# DOT_LED.net
KiCad netlist of a schematic drawn in Altium Designer
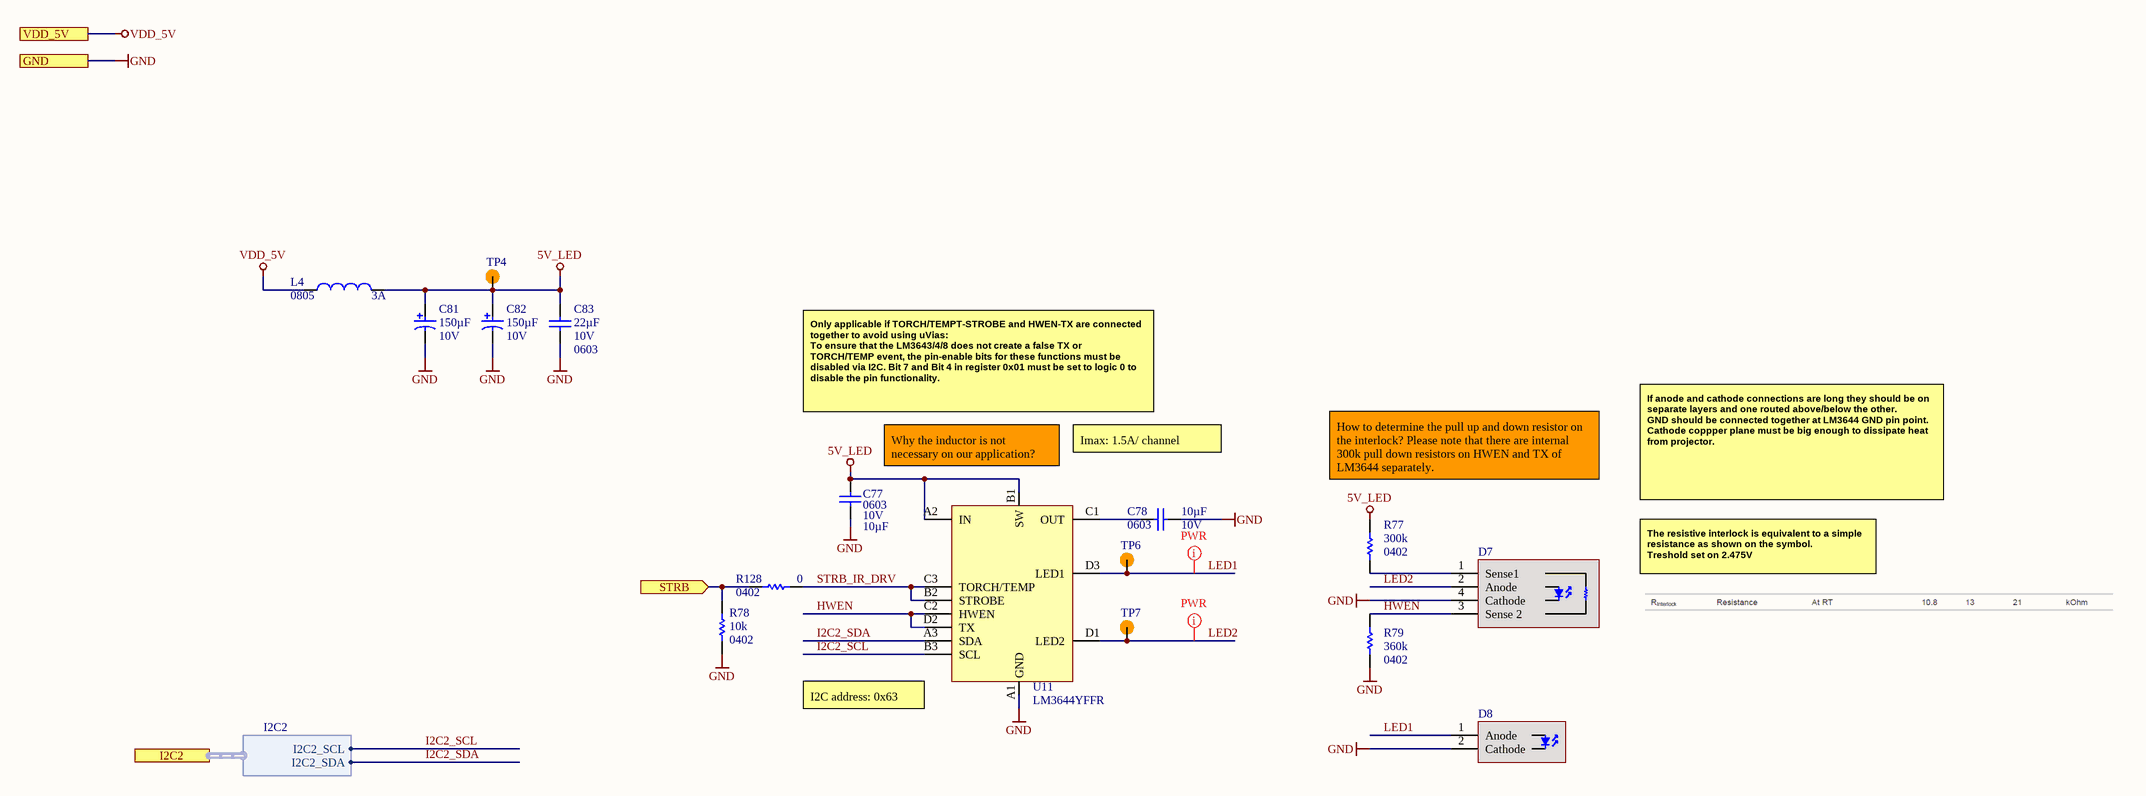
[diagram p0: DOT_LED.SchDoc]

(export (version "E")
  (design (tool "Eeschema 10.0.6"))
  (components
    (comp (ref "C77")
      (value "10µF")
      (footprint "CAPC0603(1608)100_L")
      (description "CAP CER 10UF 10V X5R 0603 20%")
      (fields
        (field (name "CASE/PACKAGE") "0603")
        (field (name "TOLERANCE") "20%")
        (field (name "VOLTAGE RATING") "10V")
        (field (name "Comment") "GRM188R61A106ME69D")
      )
      (libsource (lib "Luxonis LLC") (part "LLL153C70G474ME17E"))
    )
    (comp (ref "C78")
      (value "10µF")
      (footprint "CAPC0603(1608)100_L")
      (description "CAP CER 10UF 10V X5R 0603 20%")
      (fields
        (field (name "CASE/PACKAGE") "0603")
        (field (name "TOLERANCE") "20%")
        (field (name "VOLTAGE RATING") "10V")
        (field (name "Comment") "GRM188R61A106ME69D")
      )
      (libsource (lib "Luxonis LLC") (part "LLL153C70G474ME17E"))
    )
    (comp (ref "C81")
      (value "150µF")
      (footprint "RESTL1210(3225)_L")
      (description "CAP TAL 150UF 10V 20%")
      (fields
        (field (name "TOLERANCE") "20%")
        (field (name "VOLTAGE RATING") "10V")
        (field (name "Comment") "TLJB157M010R0500")
      )
      (libsource (lib "Luxonis LLC") (part "TLJB157M010R0500"))
    )
    (comp (ref "C82")
      (value "150µF")
      (footprint "RESTL1210(3225)_L")
      (description "CAP TAL 150UF 10V 20%")
      (fields
        (field (name "TOLERANCE") "20%")
        (field (name "VOLTAGE RATING") "10V")
        (field (name "Comment") "TLJB157M010R0500")
      )
      (libsource (lib "Luxonis LLC") (part "TLJB157M010R0500"))
    )
    (comp (ref "C83")
      (value "22µF")
      (footprint "CAPC0603(1608)100_N")
      (description "CAP CER 22UF 10V X5R 0603 20%")
      (fields
        (field (name "VOLTAGE RATING") "10V")
        (field (name "TOLERANCE") "20%")
        (field (name "CASE/PACKAGE") "0603")
        (field (name "Comment") "GRM188R61A226ME15D")
      )
      (libsource (lib "Luxonis LLC") (part "GRM188R61C475KAAJD"))
    )
    (comp (ref "D7")
      (value "BELAGO1.1")
      (footprint "Belago1.1")
      (description "Dot-Pattern Infrared Illuminator for 3D Stereoscopic\r\nImaging AQAA-20")
      (libsource (lib "Luxonis LLC") (part "BELAGO1.1"))
    )
    (comp (ref "D8")
      (value "SFH 4725AS")
      (footprint "SFH 4715AS")
      (description "OSLON Black Series (940 nm) - 80°")
      (libsource (lib "Luxonis LLC") (part "SFH 4725AS"))
    )
    (comp (ref "L4")
      (value "742792011")
      (footprint "SMD-0805")
      (description "Ferrite Chip, 1 Function(s), 3A, 2 Pin(s)")
      (fields (field (name "CURRENT RATING") "3A") (field (name "CASE/PACKAGE") "0805"))
      (libsource (lib "Luxonis LLC") (part "IND-2"))
    )
    (comp (ref "R77")
      (value "300k")
      (footprint "RESC0402(1005)_N")
      (description "RES SMD 300K OHM 1% 1/16W 0402")
      (fields
        (field (name "CASE/PACKAGE") "0402")
        (field (name "TOLERANCE") "1%")
        (field (name "Comment") "RC0402FR-07300KL")
      )
      (libsource (lib "Luxonis LLC") (part "Default resistor symbol"))
    )
    (comp (ref "R78")
      (value "10k")
      (footprint "RESC0402(1005)_N")
      (description "RES SMD 10K OHM 1% 1/16W 0402")
      (fields
        (field (name "CASE/PACKAGE") "0402")
        (field (name "TOLERANCE") "1%")
        (field (name "Comment") "RC0402FR-1310KL")
      )
      (libsource (lib "Luxonis LLC") (part "RC0402FR-0722RL_1"))
    )
    (comp (ref "R79")
      (value "360k")
      (footprint "RESC0402(1005)_N")
      (description "RES SMD 360K OHM 1% 1/16W 0402")
      (fields
        (field (name "CASE/PACKAGE") "0402")
        (field (name "TOLERANCE") "1%")
        (field (name "Comment") "RC0402FR-07360KL")
      )
      (libsource (lib "Luxonis LLC") (part "Default resistor symbol"))
    )
    (comp (ref "R128")
      (value "0")
      (footprint "RESC0402(1005)_L")
      (description "RES SMD 0 OHM 5% 1/16W 0402")
      (fields
        (field (name "CASE/PACKAGE") "0402")
        (field (name "TOLERANCE") "5%")
        (field (name "Comment") "CRCW04020000Z0ED")
      )
      (libsource (lib "Luxonis LLC") (part "Default resistor symbol"))
    )
    (comp (ref "TP4")
      (value "TEST_POINT")
      (footprint "TP075_150_NS")
      (libsource (lib "Luxonis LLC") (part "TEST_POINT"))
    )
    (comp (ref "TP6")
      (value "TEST_POINT")
      (footprint "TP075_150_NS")
      (libsource (lib "Luxonis LLC") (part "TEST_POINT"))
    )
    (comp (ref "TP7")
      (value "TEST_POINT")
      (footprint "TP075_150_NS")
      (libsource (lib "Luxonis LLC") (part "TEST_POINT"))
    )
    (comp (ref "U11")
      (value "LM3644YFFR")
      (footprint "LM3644YFFR")
      (description "LED Driver, 2-Segment, PBGA12")
      (libsource (lib "Luxonis LLC") (part "LM3644"))
    )
  )
  (nets
    (net (code "2") (name "/HWEN") (class "Default")
      (node (ref "D7") (pin "3") (pinfunction "Sense_2_3") (pintype "passive"))
      (node (ref "R79") (pin "2") (pinfunction "2_2") (pintype "passive"))
      (node (ref "U11") (pin "C2") (pinfunction "HWEN_C2") (pintype "passive"))
      (node (ref "U11") (pin "D2") (pinfunction "TX_D2") (pintype "passive"))
    )
    (net (code "3") (name "/I2C2_SCL") (class "Default")
      (node (ref "U11") (pin "B3") (pinfunction "SCL_B3") (pintype "passive"))
    )
    (net (code "4") (name "/I2C2_SDA") (class "Default")
      (node (ref "U11") (pin "A3") (pinfunction "SDA_A3") (pintype "passive"))
    )
    (net (code "5") (name "/LED1") (class "Default")
      (node (ref "D8") (pin "1") (pinfunction "Anode_1") (pintype "passive"))
      (node (ref "TP6") (pin "1") (pintype "passive"))
      (node (ref "U11") (pin "D3") (pinfunction "LED1_D3") (pintype "passive"))
    )
    (net (code "6") (name "/LED2") (class "Default")
      (node (ref "D7") (pin "2") (pinfunction "Anode_2") (pintype "passive"))
      (node (ref "TP7") (pin "1") (pintype "passive"))
      (node (ref "U11") (pin "D1") (pinfunction "LED2_D1") (pintype "passive"))
    )
    (net (code "7") (name "/STRB") (class "Default")
      (node (ref "R128") (pin "2") (pinfunction "2_2") (pintype "passive"))
      (node (ref "R78") (pin "2") (pinfunction "2_2") (pintype "passive"))
    )
    (net (code "8") (name "/STRB_IR_DRV") (class "Default")
      (node (ref "R128") (pin "1") (pinfunction "1_1") (pintype "passive"))
      (node (ref "U11") (pin "B2") (pinfunction "STROBE_B2") (pintype "passive"))
      (node (ref "U11") (pin "C3") (pinfunction "TORCH/TEMP_C3") (pintype "passive"))
    )
    (net (code "10") (name "5V_LED") (class "Default")
      (node (ref "C77") (pin "2") (pinfunction "2_2") (pintype "passive"))
      (node (ref "C81") (pin "1") (pinfunction "1_1") (pintype "passive"))
      (node (ref "C82") (pin "1") (pinfunction "1_1") (pintype "passive"))
      (node (ref "C83") (pin "2") (pinfunction "2_2") (pintype "passive"))
      (node (ref "L4") (pin "2") (pinfunction "2_2") (pintype "passive"))
      (node (ref "R77") (pin "2") (pinfunction "2_2") (pintype "passive"))
      (node (ref "TP4") (pin "1") (pintype "passive"))
      (node (ref "U11") (pin "A2") (pinfunction "IN_A2") (pintype "passive"))
      (node (ref "U11") (pin "B1") (pinfunction "SW_B1") (pintype "passive"))
    )
    (net (code "11") (name "GND") (class "Default")
      (node (ref "C77") (pin "1") (pinfunction "1_1") (pintype "passive"))
      (node (ref "C78") (pin "2") (pinfunction "2_2") (pintype "passive"))
      (node (ref "C81") (pin "2") (pinfunction "2_2") (pintype "passive"))
      (node (ref "C82") (pin "2") (pinfunction "2_2") (pintype "passive"))
      (node (ref "C83") (pin "1") (pinfunction "1_1") (pintype "passive"))
      (node (ref "D7") (pin "4") (pinfunction "Cathode_4") (pintype "passive"))
      (node (ref "D8") (pin "2") (pinfunction "Cathode_2") (pintype "passive"))
      (node (ref "R78") (pin "1") (pinfunction "1_1") (pintype "passive"))
      (node (ref "R79") (pin "1") (pinfunction "1_1") (pintype "passive"))
      (node (ref "U11") (pin "A1") (pinfunction "GND_A1") (pintype "passive"))
    )
    (net (code "12") (name "Net-(D7-Sense1)") (class "Default")
      (node (ref "D7") (pin "1") (pinfunction "Sense1_1") (pintype "passive"))
      (node (ref "R77") (pin "1") (pinfunction "1_1") (pintype "passive"))
    )
    (net (code "13") (name "Net-(U11-OUT)") (class "Default")
      (node (ref "C78") (pin "1") (pinfunction "1_1") (pintype "passive"))
      (node (ref "U11") (pin "C1") (pinfunction "OUT_C1") (pintype "passive"))
    )
    (net (code "14") (name "VDD_5V") (class "Default")
      (node (ref "L4") (pin "1") (pinfunction "1_1") (pintype "passive"))
    )
  )
)
